# Temperatura_y_humedad.net
KiCad netlist of a schematic drawn in EAGLE
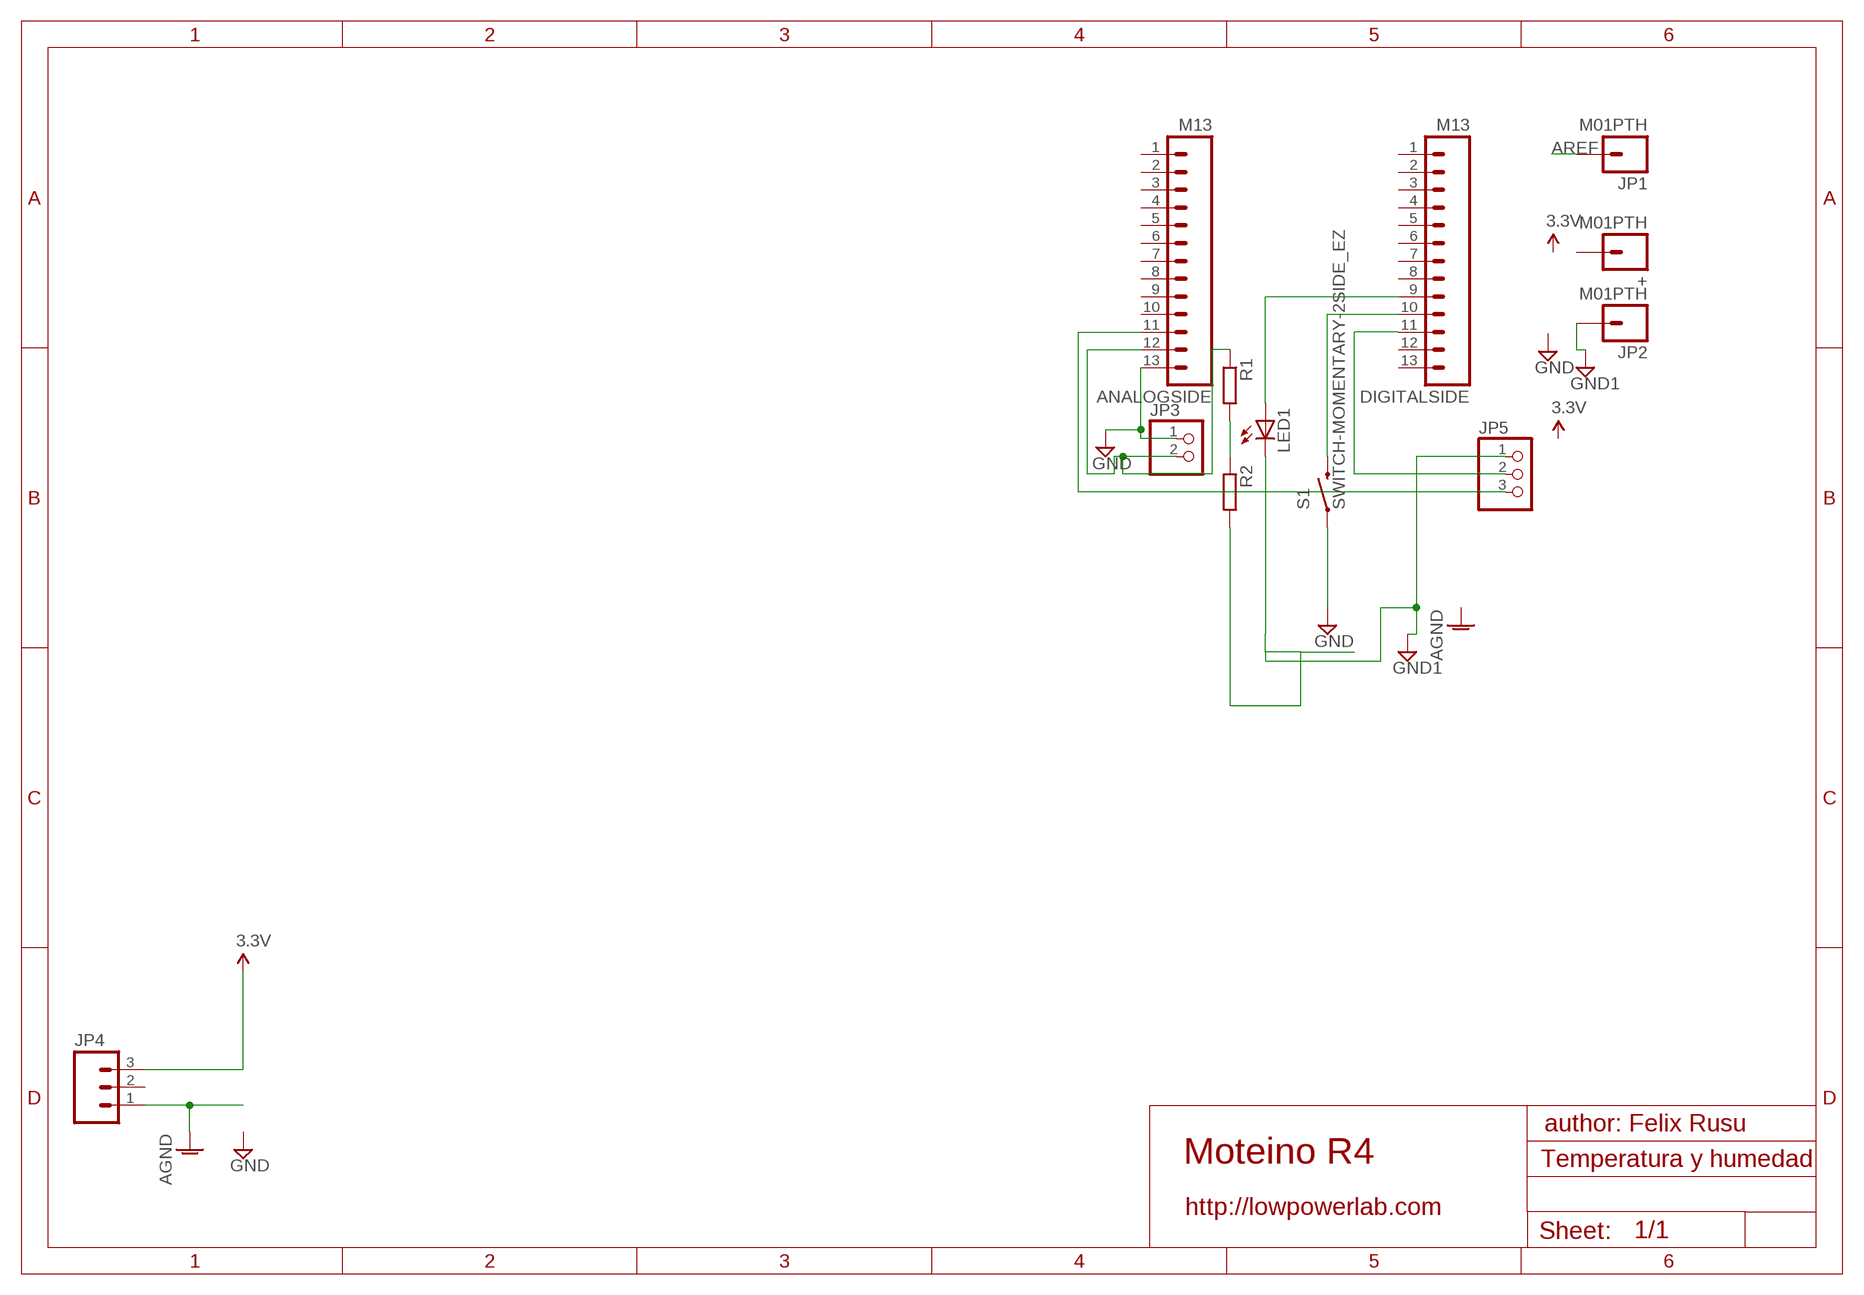
[diagram p0: schematic, sheet 1]

(export (version "E")
  (design (tool "Eeschema 10.0.6"))
  (components
    (comp (ref "+")
      (value "M01PTH")
      (footprint "eagle-import:1X01")
      (libsource (lib "eagle-import") (part "M01PTH"))
    )
    (comp (ref "ANALOGSIDE")
      (value "M13")
      (footprint "eagle-import:1X13")
      (libsource (lib "eagle-import") (part "M13"))
    )
    (comp (ref "DIGITALSIDE")
      (value "M13")
      (footprint "eagle-import:1X13")
      (libsource (lib "eagle-import") (part "M13"))
    )
    (comp (ref "JP1")
      (value "M01PTH")
      (footprint "eagle-import:1X01")
      (libsource (lib "eagle-import") (part "M01PTH"))
    )
    (comp (ref "JP2")
      (value "M01PTH")
      (footprint "eagle-import:1X01")
      (libsource (lib "eagle-import") (part "M01PTH"))
    )
    (comp (ref "JP3")
      (value "PINHD-1X2")
      (footprint "eagle-import:1X02")
      (libsource (lib "eagle-import") (part "PINHD-1X2"))
    )
    (comp (ref "JP4")
      (value "M03PTH")
      (footprint "eagle-import:1X03")
      (libsource (lib "eagle-import") (part "M03PTH"))
    )
    (comp (ref "JP5")
      (value "PINHD-1X3")
      (footprint "eagle-import:1X03")
      (libsource (lib "eagle-import") (part "PINHD-1X3"))
    )
    (comp (ref "LED1")
      (value "LED3MM")
      (footprint "eagle-import:LED3MM")
      (libsource (lib "eagle-import") (part "LED3MM"))
    )
    (comp (ref "R1")
      (value "R-EU_0204/7")
      (footprint "eagle-import:0204_7")
      (libsource (lib "eagle-import") (part "R-EU_0204/7"))
    )
    (comp (ref "R2")
      (value "R-EU_0204/7")
      (footprint "eagle-import:0204_7")
      (libsource (lib "eagle-import") (part "R-EU_0204/7"))
    )
    (comp (ref "S1")
      (value "SWITCH-MOMENTARY-2SIDE_EZ")
      (footprint "eagle-import:TACTILE-PTH-SIDEEZ")
      (libsource (lib "eagle-import") (part "SWITCH-MOMENTARY-2SIDE_EZ"))
    )
  )
  (nets
    (net (code "1") (name "/AREF") (class "Default")
      (node (ref "JP1") (pin "1") (pinfunction "1_1") (pintype "passive"))
    )
    (net (code "2") (name "3.3V") (class "Default")
      (node (ref "JP4") (pin "3") (pinfunction "3_3") (pintype "passive"))
    )
    (net (code "3") (name "AGND") (class "Default")
      (node (ref "JP4") (pin "1") (pinfunction "1_1") (pintype "passive"))
    )
    (net (code "4") (name "GND") (class "Default")
      (node (ref "ANALOGSIDE") (pin "13") (pinfunction "13_13") (pintype "passive"))
      (node (ref "JP3") (pin "1") (pinfunction "1_1") (pintype "passive"))
      (node (ref "S1") (pin "1") (pinfunction "1_1") (pintype "passive"))
    )
    (net (code "5") (name "GND1") (class "Default")
      (node (ref "JP2") (pin "1") (pinfunction "1_1") (pintype "passive"))
      (node (ref "JP5") (pin "1") (pinfunction "1_1") (pintype "passive"))
      (node (ref "LED1") (pin "K") (pinfunction "C_K") (pintype "passive"))
      (node (ref "R2") (pin "2") (pinfunction "2_2") (pintype "passive"))
    )
    (net (code "6") (name "Net-(ANALOGSIDE-Pad11)") (class "Default")
      (node (ref "ANALOGSIDE") (pin "11") (pinfunction "11_11") (pintype "passive"))
      (node (ref "JP5") (pin "3") (pinfunction "3_3") (pintype "passive"))
    )
    (net (code "7") (name "Net-(ANALOGSIDE-Pad12)") (class "Default")
      (node (ref "ANALOGSIDE") (pin "12") (pinfunction "12_12") (pintype "passive"))
      (node (ref "JP3") (pin "2") (pinfunction "2_2") (pintype "passive"))
      (node (ref "R1") (pin "1") (pinfunction "1_1") (pintype "passive"))
    )
    (net (code "8") (name "Net-(DIGITALSIDE-Pad9)") (class "Default")
      (node (ref "DIGITALSIDE") (pin "9") (pinfunction "9_9") (pintype "passive"))
      (node (ref "LED1") (pin "A") (pinfunction "A_A") (pintype "passive"))
    )
    (net (code "9") (name "Net-(DIGITALSIDE-Pad10)") (class "Default")
      (node (ref "DIGITALSIDE") (pin "10") (pinfunction "10_10") (pintype "passive"))
      (node (ref "S1") (pin "2") (pinfunction "2_2") (pintype "passive"))
    )
    (net (code "10") (name "Net-(DIGITALSIDE-Pad11)") (class "Default")
      (node (ref "DIGITALSIDE") (pin "11") (pinfunction "11_11") (pintype "passive"))
      (node (ref "JP5") (pin "2") (pinfunction "2_2") (pintype "passive"))
    )
    (net (code "11") (name "Net-(R1-Pad2)") (class "Default")
      (node (ref "R1") (pin "2") (pinfunction "2_2") (pintype "passive"))
      (node (ref "R2") (pin "1") (pinfunction "1_1") (pintype "passive"))
    )
    (net (code "12") (name "unconnected-(+-Pad1)") (class "Default")
      (node (ref "+") (pin "1") (pinfunction "1_1") (pintype "passive"))
    )
    (net (code "13") (name "unconnected-(ANALOGSIDE-Pad1)") (class "Default")
      (node (ref "ANALOGSIDE") (pin "1") (pinfunction "1_1") (pintype "passive"))
    )
    (net (code "14") (name "unconnected-(ANALOGSIDE-Pad2)") (class "Default")
      (node (ref "ANALOGSIDE") (pin "2") (pinfunction "2_2") (pintype "passive"))
    )
    (net (code "15") (name "unconnected-(ANALOGSIDE-Pad3)") (class "Default")
      (node (ref "ANALOGSIDE") (pin "3") (pinfunction "3_3") (pintype "passive"))
    )
    (net (code "16") (name "unconnected-(ANALOGSIDE-Pad4)") (class "Default")
      (node (ref "ANALOGSIDE") (pin "4") (pinfunction "4_4") (pintype "passive"))
    )
    (net (code "17") (name "unconnected-(ANALOGSIDE-Pad5)") (class "Default")
      (node (ref "ANALOGSIDE") (pin "5") (pinfunction "5_5") (pintype "passive"))
    )
    (net (code "18") (name "unconnected-(ANALOGSIDE-Pad6)") (class "Default")
      (node (ref "ANALOGSIDE") (pin "6") (pinfunction "6_6") (pintype "passive"))
    )
    (net (code "19") (name "unconnected-(ANALOGSIDE-Pad7)") (class "Default")
      (node (ref "ANALOGSIDE") (pin "7") (pinfunction "7_7") (pintype "passive"))
    )
    (net (code "20") (name "unconnected-(ANALOGSIDE-Pad8)") (class "Default")
      (node (ref "ANALOGSIDE") (pin "8") (pinfunction "8_8") (pintype "passive"))
    )
    (net (code "21") (name "unconnected-(ANALOGSIDE-Pad9)") (class "Default")
      (node (ref "ANALOGSIDE") (pin "9") (pinfunction "9_9") (pintype "passive"))
    )
    (net (code "22") (name "unconnected-(ANALOGSIDE-Pad10)") (class "Default")
      (node (ref "ANALOGSIDE") (pin "10") (pinfunction "10_10") (pintype "passive"))
    )
    (net (code "23") (name "unconnected-(DIGITALSIDE-Pad1)") (class "Default")
      (node (ref "DIGITALSIDE") (pin "1") (pinfunction "1_1") (pintype "passive"))
    )
    (net (code "24") (name "unconnected-(DIGITALSIDE-Pad2)") (class "Default")
      (node (ref "DIGITALSIDE") (pin "2") (pinfunction "2_2") (pintype "passive"))
    )
    (net (code "25") (name "unconnected-(DIGITALSIDE-Pad3)") (class "Default")
      (node (ref "DIGITALSIDE") (pin "3") (pinfunction "3_3") (pintype "passive"))
    )
    (net (code "26") (name "unconnected-(DIGITALSIDE-Pad4)") (class "Default")
      (node (ref "DIGITALSIDE") (pin "4") (pinfunction "4_4") (pintype "passive"))
    )
    (net (code "27") (name "unconnected-(DIGITALSIDE-Pad5)") (class "Default")
      (node (ref "DIGITALSIDE") (pin "5") (pinfunction "5_5") (pintype "passive"))
    )
    (net (code "28") (name "unconnected-(DIGITALSIDE-Pad6)") (class "Default")
      (node (ref "DIGITALSIDE") (pin "6") (pinfunction "6_6") (pintype "passive"))
    )
    (net (code "29") (name "unconnected-(DIGITALSIDE-Pad7)") (class "Default")
      (node (ref "DIGITALSIDE") (pin "7") (pinfunction "7_7") (pintype "passive"))
    )
    (net (code "30") (name "unconnected-(DIGITALSIDE-Pad8)") (class "Default")
      (node (ref "DIGITALSIDE") (pin "8") (pinfunction "8_8") (pintype "passive"))
    )
    (net (code "31") (name "unconnected-(DIGITALSIDE-Pad12)") (class "Default")
      (node (ref "DIGITALSIDE") (pin "12") (pinfunction "12_12") (pintype "passive"))
    )
    (net (code "32") (name "unconnected-(DIGITALSIDE-Pad13)") (class "Default")
      (node (ref "DIGITALSIDE") (pin "13") (pinfunction "13_13") (pintype "passive"))
    )
    (net (code "33") (name "unconnected-(JP4-Pad2)") (class "Default")
      (node (ref "JP4") (pin "2") (pinfunction "2_2") (pintype "passive"))
    )
  )
)
